# sensor.net
KiCad netlist of a schematic drawn in EAGLE
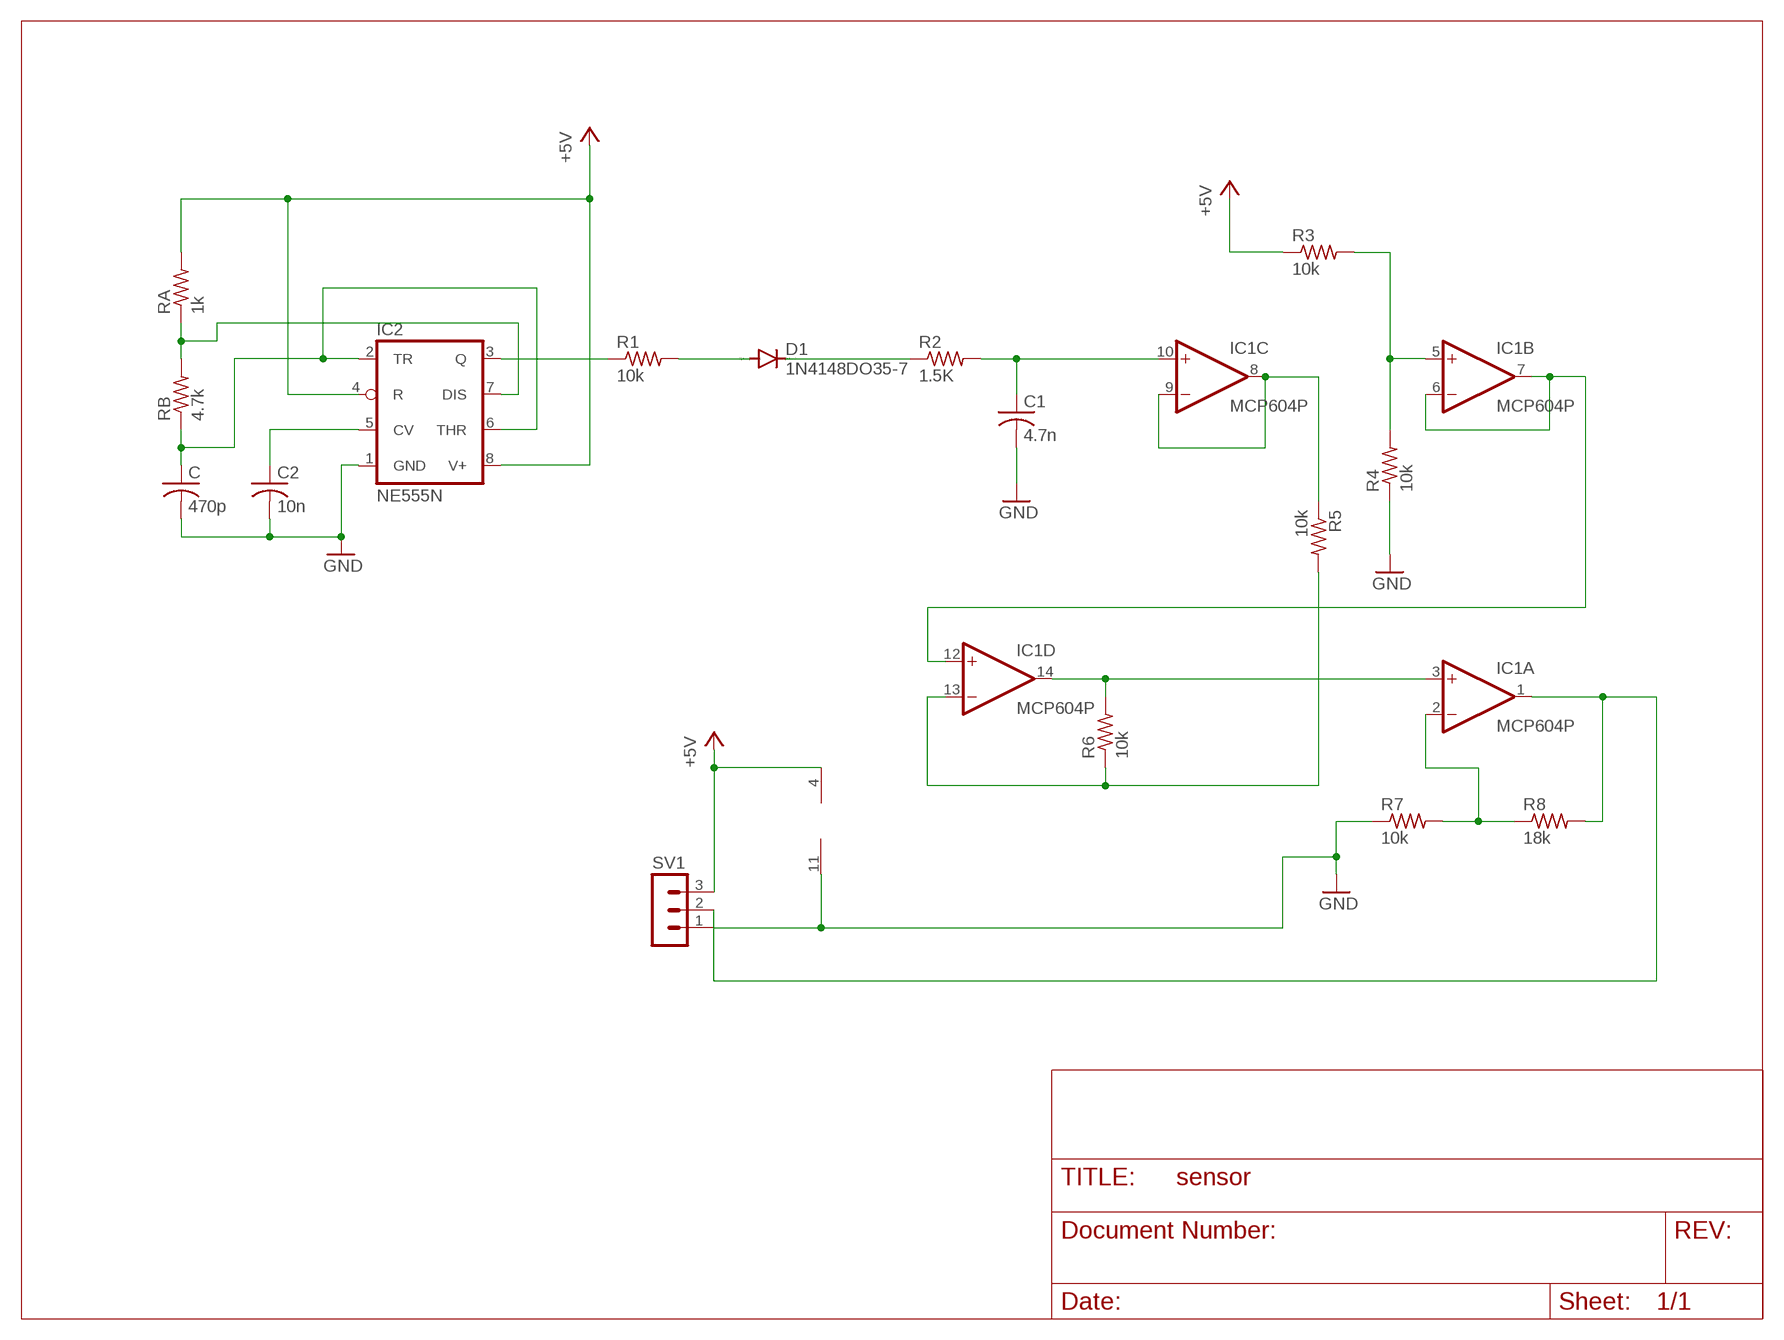
[diagram p0: schematic, sheet 1]

(export (version "E")
  (design (tool "Eeschema 10.0.6"))
  (components
    (comp (ref "C")
      (value "470p")
      (footprint "eagle-import:C025-024X044")
      (libsource (lib "eagle-import") (part "C-US025-024X044"))
    )
    (comp (ref "C1")
      (value "4.7n")
      (footprint "eagle-import:C025-024X044")
      (libsource (lib "eagle-import") (part "C-US025-024X044"))
    )
    (comp (ref "C2")
      (value "10n")
      (footprint "eagle-import:C025-024X044")
      (libsource (lib "eagle-import") (part "C-US025-024X044"))
    )
    (comp (ref "D1")
      (value "1N4148DO35-7")
      (footprint "eagle-import:DO35-7")
      (libsource (lib "eagle-import") (part "1N4148DO35-7"))
    )
    (comp (ref "IC1")
      (value "MCP604P")
      (footprint "eagle-import:DIL14")
      (libsource (lib "eagle-import") (part "MCP604P"))
    )
    (comp (ref "IC2")
      (value "NE555N")
      (footprint "eagle-import:DIL08")
      (libsource (lib "eagle-import") (part "555NNE"))
    )
    (comp (ref "R1")
      (value "10k")
      (footprint "eagle-import:0204_7")
      (libsource (lib "eagle-import") (part "R-US_0204/7"))
    )
    (comp (ref "R2")
      (value "1.5K")
      (footprint "eagle-import:0204_7")
      (libsource (lib "eagle-import") (part "R-US_0204/7"))
    )
    (comp (ref "R3")
      (value "10k")
      (footprint "eagle-import:0204_7")
      (libsource (lib "eagle-import") (part "R-US_0204/7"))
    )
    (comp (ref "R4")
      (value "10k")
      (footprint "eagle-import:0204_7")
      (libsource (lib "eagle-import") (part "R-US_0204/7"))
    )
    (comp (ref "R5")
      (value "10k")
      (footprint "eagle-import:0204_7")
      (libsource (lib "eagle-import") (part "R-US_0204/7"))
    )
    (comp (ref "R6")
      (value "10k")
      (footprint "eagle-import:0204_7")
      (libsource (lib "eagle-import") (part "R-US_0204/7"))
    )
    (comp (ref "R7")
      (value "10k")
      (footprint "eagle-import:0204_7")
      (libsource (lib "eagle-import") (part "R-US_0204/7"))
    )
    (comp (ref "R8")
      (value "18k")
      (footprint "eagle-import:0204_7")
      (libsource (lib "eagle-import") (part "R-US_0204/7"))
    )
    (comp (ref "RA")
      (value "1k")
      (footprint "eagle-import:0204_7")
      (libsource (lib "eagle-import") (part "R-US_0204/7"))
    )
    (comp (ref "RB")
      (value "4.7k")
      (footprint "eagle-import:0204_7")
      (libsource (lib "eagle-import") (part "R-US_0204/7"))
    )
    (comp (ref "SV1")
      (value "MA03-1")
      (footprint "eagle-import:MA03-1")
      (libsource (lib "eagle-import") (part "MA03-1"))
    )
  )
  (nets
    (net (code "1") (name "+5V") (class "Default")
      (node (ref "IC1") (pin "4") (pinfunction "V+_4") (pintype "power_in"))
      (node (ref "IC2") (pin "4") (pinfunction "R_4") (pintype "input"))
      (node (ref "IC2") (pin "8") (pinfunction "V+_8") (pintype "power_in"))
      (node (ref "R3") (pin "1") (pinfunction "1_1") (pintype "passive"))
      (node (ref "RA") (pin "2") (pinfunction "2_2") (pintype "passive"))
      (node (ref "SV1") (pin "3") (pinfunction "3_3") (pintype "passive"))
    )
    (net (code "2") (name "GND") (class "Default")
      (node (ref "C") (pin "2") (pinfunction "2_2") (pintype "passive"))
      (node (ref "C1") (pin "2") (pinfunction "2_2") (pintype "passive"))
      (node (ref "C2") (pin "2") (pinfunction "2_2") (pintype "passive"))
      (node (ref "IC1") (pin "11") (pinfunction "V-_11") (pintype "power_in"))
      (node (ref "IC2") (pin "1") (pinfunction "GND_1") (pintype "power_in"))
      (node (ref "R4") (pin "1") (pinfunction "1_1") (pintype "passive"))
      (node (ref "R7") (pin "1") (pinfunction "1_1") (pintype "passive"))
      (node (ref "SV1") (pin "1") (pinfunction "1_1") (pintype "passive"))
    )
    (net (code "3") (name "Net-(D1-PadA)") (class "Default")
      (node (ref "D1") (pin "A") (pinfunction "A_A") (pintype "passive"))
      (node (ref "R1") (pin "2") (pinfunction "2_2") (pintype "passive"))
    )
    (net (code "4") (name "Net-(D1-PadC)") (class "Default")
      (node (ref "D1") (pin "C") (pinfunction "C_C") (pintype "passive"))
      (node (ref "R2") (pin "1") (pinfunction "1_1") (pintype "passive"))
    )
    (net (code "5") (name "Net-(IC1A-+IN)") (class "Default")
      (node (ref "IC1") (pin "14") (pinfunction "OUT_14") (pintype "output"))
      (node (ref "IC1") (pin "3") (pinfunction "+IN_3") (pintype "input"))
      (node (ref "R6") (pin "2") (pinfunction "2_2") (pintype "passive"))
    )
    (net (code "6") (name "Net-(IC1A--IN)") (class "Default")
      (node (ref "IC1") (pin "2") (pinfunction "-IN_2") (pintype "input"))
      (node (ref "R7") (pin "2") (pinfunction "2_2") (pintype "passive"))
      (node (ref "R8") (pin "1") (pinfunction "1_1") (pintype "passive"))
    )
    (net (code "7") (name "Net-(IC1A-OUT)") (class "Default")
      (node (ref "IC1") (pin "1") (pinfunction "OUT_1") (pintype "output"))
      (node (ref "R8") (pin "2") (pinfunction "2_2") (pintype "passive"))
      (node (ref "SV1") (pin "2") (pinfunction "2_2") (pintype "passive"))
    )
    (net (code "8") (name "Net-(IC1B-+IN)") (class "Default")
      (node (ref "IC1") (pin "5") (pinfunction "+IN_5") (pintype "input"))
      (node (ref "R3") (pin "2") (pinfunction "2_2") (pintype "passive"))
      (node (ref "R4") (pin "2") (pinfunction "2_2") (pintype "passive"))
    )
    (net (code "9") (name "Net-(IC1B--IN)") (class "Default")
      (node (ref "IC1") (pin "12") (pinfunction "+IN_12") (pintype "input"))
      (node (ref "IC1") (pin "6") (pinfunction "-IN_6") (pintype "input"))
      (node (ref "IC1") (pin "7") (pinfunction "OUT_7") (pintype "output"))
    )
    (net (code "10") (name "Net-(IC1C-+IN)") (class "Default")
      (node (ref "C1") (pin "1") (pinfunction "1_1") (pintype "passive"))
      (node (ref "IC1") (pin "10") (pinfunction "+IN_10") (pintype "input"))
      (node (ref "R2") (pin "2") (pinfunction "2_2") (pintype "passive"))
    )
    (net (code "11") (name "Net-(IC1C--IN)") (class "Default")
      (node (ref "IC1") (pin "8") (pinfunction "OUT_8") (pintype "output"))
      (node (ref "IC1") (pin "9") (pinfunction "-IN_9") (pintype "input"))
      (node (ref "R5") (pin "1") (pinfunction "1_1") (pintype "passive"))
    )
    (net (code "12") (name "Net-(IC1D--IN)") (class "Default")
      (node (ref "IC1") (pin "13") (pinfunction "-IN_13") (pintype "input"))
      (node (ref "R5") (pin "2") (pinfunction "2_2") (pintype "passive"))
      (node (ref "R6") (pin "1") (pinfunction "1_1") (pintype "passive"))
    )
    (net (code "13") (name "Net-(IC2-CV)") (class "Default")
      (node (ref "C2") (pin "1") (pinfunction "1_1") (pintype "passive"))
      (node (ref "IC2") (pin "5") (pinfunction "CV_5") (pintype "input"))
    )
    (net (code "14") (name "Net-(IC2-DIS)") (class "Default")
      (node (ref "IC2") (pin "7") (pinfunction "DIS_7") (pintype "input"))
      (node (ref "RA") (pin "1") (pinfunction "1_1") (pintype "passive"))
      (node (ref "RB") (pin "2") (pinfunction "2_2") (pintype "passive"))
    )
    (net (code "15") (name "Net-(IC2-Q)") (class "Default")
      (node (ref "IC2") (pin "3") (pinfunction "Q_3") (pintype "output"))
      (node (ref "R1") (pin "1") (pinfunction "1_1") (pintype "passive"))
    )
    (net (code "16") (name "Net-(IC2-THR)") (class "Default")
      (node (ref "C") (pin "1") (pinfunction "1_1") (pintype "passive"))
      (node (ref "IC2") (pin "2") (pinfunction "TR_2") (pintype "input"))
      (node (ref "IC2") (pin "6") (pinfunction "THR_6") (pintype "input"))
      (node (ref "RB") (pin "1") (pinfunction "1_1") (pintype "passive"))
    )
  )
)
